# Karduino_Sch.net
KiCad netlist of a schematic drawn in Altium Designer
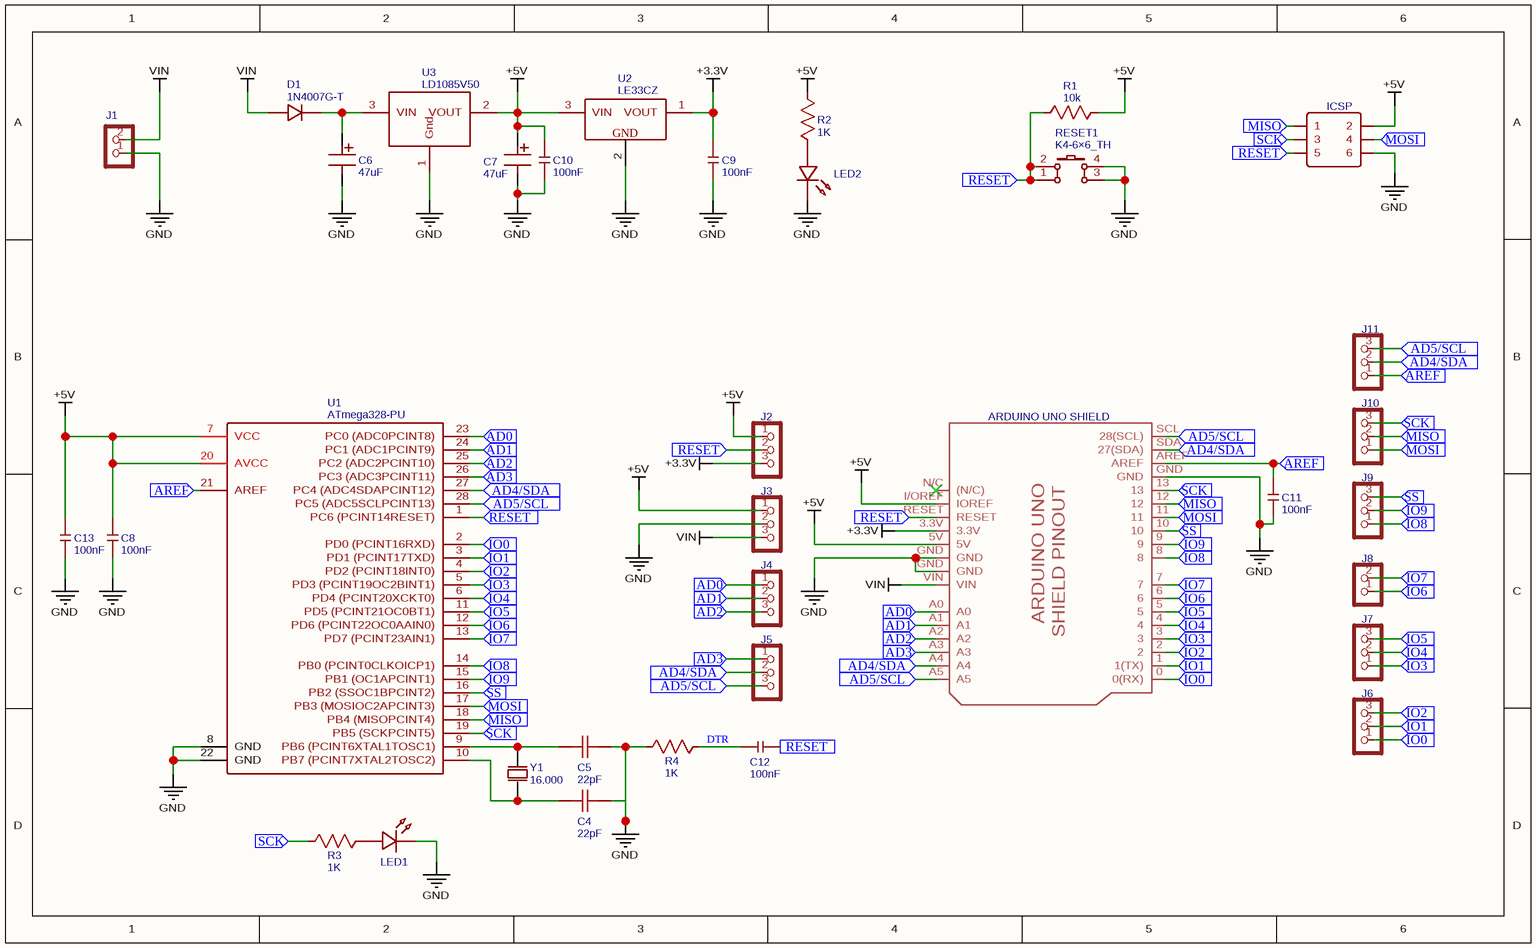
[diagram p0: Karduino_Sch.schdoc]

(export (version "E")
  (design (tool "Eeschema 10.0.6"))
  (components
    (comp (ref "C4")
      (value "22pF")
      (fields
        (field (name "MANUFACTURER") "TORCH(火炬)")
        (field (name "MANUFACTURER PART") "CC4-0805-CG-50V-22pF-J")
        (field (name "CONTRIBUTOR") "LCSC")
      )
      (libsource (lib "altium-import") (part "root_0_22pF_"))
    )
    (comp (ref "C5")
      (value "22pF")
      (fields
        (field (name "MANUFACTURER") "TORCH(火炬)")
        (field (name "MANUFACTURER PART") "CC4-0805-CG-50V-22pF-J")
        (field (name "CONTRIBUTOR") "LCSC")
      )
      (libsource (lib "altium-import") (part "root_0_22pF_"))
    )
    (comp (ref "C6")
      (value "47uF")
      (fields
        (field (name "VOLTAGE") "25V")
        (field (name "TOLERANCE") "±20%")
        (field (name "MANUFACTURER") "MULTICOMP")
        (field (name "CONTRIBUTOR") "Prof. Ing. F. Scordino")
      )
      (libsource (lib "altium-import") (part "root_3_47uF_"))
    )
    (comp (ref "C7")
      (value "47uF")
      (fields
        (field (name "VOLTAGE") "25V")
        (field (name "TOLERANCE") "±20%")
        (field (name "MANUFACTURER") "MULTICOMP")
        (field (name "CONTRIBUTOR") "Prof. Ing. F. Scordino")
      )
      (libsource (lib "altium-import") (part "root_3_47uF_"))
    )
    (comp (ref "C8")
      (value "100nF")
      (description "302010208")
      (fields (field (name "CONTRIBUTOR") "pitpossum 79"))
      (libsource (lib "altium-import") (part "root_1_100nF_"))
    )
    (comp (ref "C9")
      (value "100nF")
      (description "302010208")
      (fields (field (name "CONTRIBUTOR") "pitpossum 79"))
      (libsource (lib "altium-import") (part "root_1_100nF_"))
    )
    (comp (ref "C10")
      (value "100nF")
      (description "302010208")
      (fields (field (name "CONTRIBUTOR") "pitpossum 79"))
      (libsource (lib "altium-import") (part "root_1_100nF_"))
    )
    (comp (ref "C11")
      (value "100nF")
      (description "302010208")
      (fields (field (name "CONTRIBUTOR") "pitpossum 79"))
      (libsource (lib "altium-import") (part "root_1_100nF_"))
    )
    (comp (ref "C12")
      (value "100nF")
      (description "302010208")
      (fields (field (name "CONTRIBUTOR") "pitpossum 79"))
      (libsource (lib "altium-import") (part "root_0_100nF_"))
    )
    (comp (ref "C13")
      (value "100nF")
      (description "302010208")
      (fields (field (name "CONTRIBUTOR") "pitpossum 79"))
      (libsource (lib "altium-import") (part "root_1_100nF_"))
    )
    (comp (ref "D1")
      (value "1N4007G-T")
      (fields
        (field (name "MANUFACTURER") "Diodes Incorporated")
        (field (name "CONTRIBUTOR") "Habetamu Gezachew")
      )
      (libsource (lib "altium-import") (part "root_2_1N4007G-T_"))
    )
    (comp (ref "ICSP")
      (value "ICSP")
      (fields (field (name "MANUFACTURER") "BOOMELE(博穆精密)") (field (name "MANUFACTURER PART") "2.54-2*3P针"))
      (libsource (lib "altium-import") (part "root_0_ICSP_"))
    )
    (comp (ref "J1")
      (value "CON_TERMINAL_BLOCK_02-5MM")
      (description "2 poles wire to board terminal block")
      (fields (field (name "CONTRIBUTOR") "DangerousPrototype"))
      (libsource (lib "altium-import") (part "root_2_CON_TERMINAL_BLOCK_02-5MM_"))
    )
    (comp (ref "J2")
      (value "CON_TERMINAL_BLOCK_03-5MM")
      (description "3 poles, wire to board connector")
      (fields (field (name "CONTRIBUTOR") "DangerousPrototype"))
      (libsource (lib "altium-import") (part "root_0_CON_TERMINAL_BLOCK_03-5MM_"))
    )
    (comp (ref "J3")
      (value "CON_TERMINAL_BLOCK_03-5MM")
      (description "3 poles, wire to board connector")
      (fields (field (name "CONTRIBUTOR") "DangerousPrototype"))
      (libsource (lib "altium-import") (part "root_0_CON_TERMINAL_BLOCK_03-5MM_"))
    )
    (comp (ref "J4")
      (value "CON_TERMINAL_BLOCK_03-5MM")
      (description "3 poles, wire to board connector")
      (fields (field (name "CONTRIBUTOR") "DangerousPrototype"))
      (libsource (lib "altium-import") (part "root_0_CON_TERMINAL_BLOCK_03-5MM_"))
    )
    (comp (ref "J5")
      (value "CON_TERMINAL_BLOCK_03-5MM")
      (description "3 poles, wire to board connector")
      (fields (field (name "CONTRIBUTOR") "DangerousPrototype"))
      (libsource (lib "altium-import") (part "root_0_CON_TERMINAL_BLOCK_03-5MM_"))
    )
    (comp (ref "J6")
      (value "CON_TERMINAL_BLOCK_03-5MM")
      (description "3 poles, wire to board connector")
      (fields (field (name "CONTRIBUTOR") "DangerousPrototype"))
      (libsource (lib "altium-import") (part "root_2_CON_TERMINAL_BLOCK_03-5MM_"))
    )
    (comp (ref "J7")
      (value "CON_TERMINAL_BLOCK_03-5MM")
      (description "3 poles, wire to board connector")
      (fields (field (name "CONTRIBUTOR") "DangerousPrototype"))
      (libsource (lib "altium-import") (part "root_2_CON_TERMINAL_BLOCK_03-5MM_"))
    )
    (comp (ref "J8")
      (value "CON_TERMINAL_BLOCK_02-5MM")
      (description "2 poles wire to board terminal block")
      (fields (field (name "CONTRIBUTOR") "DangerousPrototype"))
      (libsource (lib "altium-import") (part "root_2_CON_TERMINAL_BLOCK_02-5MM_"))
    )
    (comp (ref "J9")
      (value "CON_TERMINAL_BLOCK_03-5MM")
      (description "3 poles, wire to board connector")
      (fields (field (name "CONTRIBUTOR") "DangerousPrototype"))
      (libsource (lib "altium-import") (part "root_2_CON_TERMINAL_BLOCK_03-5MM_"))
    )
    (comp (ref "J10")
      (value "CON_TERMINAL_BLOCK_03-5MM")
      (description "3 poles, wire to board connector")
      (fields (field (name "CONTRIBUTOR") "DangerousPrototype"))
      (libsource (lib "altium-import") (part "root_2_CON_TERMINAL_BLOCK_03-5MM_"))
    )
    (comp (ref "J11")
      (value "CON_TERMINAL_BLOCK_03-5MM")
      (description "3 poles, wire to board connector")
      (fields (field (name "CONTRIBUTOR") "DangerousPrototype"))
      (libsource (lib "altium-import") (part "root_2_CON_TERMINAL_BLOCK_03-5MM_"))
    )
    (comp (ref "LED1")
      (value "LED-TH-3mm_G")
      (fields
        (field (name "MANUFACTURER") "EVERLIGHT(台湾亿光)")
        (field (name "MANUFACTURER PART") "204-10SYGD/S530-E3")
        (field (name "CONTRIBUTOR") "LCEDA_Lib")
      )
      (libsource (lib "altium-import") (part "root_0_LED-TH-3mm_G_"))
    )
    (comp (ref "LED2")
      (value "LED-TH-3mm_R")
      (fields
        (field (name "MANUFACTURER") "EVERLIGHT(台湾亿光)")
        (field (name "MANUFACTURER PART") "204-10SDRD/S530-A3-L")
        (field (name "CONTRIBUTOR") "LCEDA_Lib")
      )
      (libsource (lib "altium-import") (part "root_3_LED-TH-3mm_R_"))
    )
    (comp (ref "PCB1")
      (value "ARDUINO UNO SHIELD")
      (fields (field (name "CONTRIBUTOR") "prodatasimulations"))
      (libsource (lib "altium-import") (part "root_0_ARDUINO UNO SHIELD_"))
    )
    (comp (ref "R1")
      (value "10k")
      (fields (field (name "CONTRIBUTOR") "LCEDA_Lib"))
      (libsource (lib "altium-import") (part "root_2_10k_"))
    )
    (comp (ref "R2")
      (value "1K")
      (fields (field (name "CONTRIBUTOR") "LCEDA_Lib"))
      (libsource (lib "altium-import") (part "root_1_1K_"))
    )
    (comp (ref "R3")
      (value "1K")
      (fields (field (name "CONTRIBUTOR") "LCEDA_Lib"))
      (libsource (lib "altium-import") (part "root_0_1K_"))
    )
    (comp (ref "R4")
      (value "1K")
      (fields (field (name "CONTRIBUTOR") "LCEDA_Lib"))
      (libsource (lib "altium-import") (part "root_0_1K_"))
    )
    (comp (ref "RESET1")
      (value "K4-6×6_TH")
      (fields
        (field (name "MANUFACTURER") "韩国韩荣")
        (field (name "MANUFACTURER PART") "K2-1102DP-E4SW-04")
        (field (name "CONTRIBUTOR") "LCEDA_Lib")
      )
      (libsource (lib "altium-import") (part "root_0_K4-6×6_TH_"))
    )
    (comp (ref "U1") (value "ATmega328-PU") (libsource (lib "altium-import") (part "root_0_ATmega328-PU_")))
    (comp (ref "U2")
      (value "LE33CZ")
      (description "Very Low Drop Voltage Regulators with Inhibit, 3.3V, 3-Pin TO92-INLINE, Tape and Reel")
      (libsource (lib "altium-import") (part "root_0_LE33CZ_"))
    )
    (comp (ref "U3")
      (value "LD1085V50")
      (fields (field (name "MANUFACTURER") "STMicroelectronics") (field (name "CONTRIBUTOR") "ih55t"))
      (libsource (lib "altium-import") (part "root_0_LD1085V50_"))
    )
    (comp (ref "Y1")
      (value "16.000")
      (fields
        (field (name "MANUFACTURER") "CTS(西迪斯)")
        (field (name "MANUFACTURER PART") "ATS098")
        (field (name "CONTRIBUTOR") "lcsc")
      )
      (libsource (lib "altium-import") (part "root_1_16.000_"))
    )
  )
  (nets
    (net (code "1") (name "+3.3V") (class "Default")
      (node (ref "C9") (pin "2") (pinfunction "2_2") (pintype "passive"))
      (node (ref "J2") (pin "3") (pinfunction "3_3") (pintype "passive"))
      (node (ref "PCB1") (pin "3.3V") (pinfunction "3.3V_3.3V") (pintype "passive"))
      (node (ref "U2") (pin "1") (pinfunction "VOUT_1") (pintype "passive"))
    )
    (net (code "2") (name "+5V") (class "Default")
      (node (ref "C10") (pin "2") (pinfunction "2_2") (pintype "passive"))
      (node (ref "C13") (pin "2") (pinfunction "2_2") (pintype "passive"))
      (node (ref "C7") (pin "1") (pinfunction "1_1") (pintype "passive"))
      (node (ref "C8") (pin "2") (pinfunction "2_2") (pintype "passive"))
      (node (ref "ICSP") (pin "2") (pinfunction "2_2") (pintype "passive"))
      (node (ref "J2") (pin "1") (pinfunction "1_1") (pintype "passive"))
      (node (ref "J3") (pin "1") (pinfunction "1_1") (pintype "passive"))
      (node (ref "PCB1") (pin "5V") (pinfunction "5V_5V") (pintype "passive"))
      (node (ref "PCB1") (pin "I/OREF") (pinfunction "IOREF_I/OREF") (pintype "passive"))
      (node (ref "R1") (pin "1") (pinfunction "1_1") (pintype "passive"))
      (node (ref "R2") (pin "2") (pinfunction "2_2") (pintype "passive"))
      (node (ref "U1") (pin "20") (pinfunction "AVCC_20") (pintype "passive"))
      (node (ref "U1") (pin "7") (pinfunction "VCC_7") (pintype "passive"))
      (node (ref "U2") (pin "3") (pinfunction "VIN_3") (pintype "passive"))
      (node (ref "U3") (pin "2") (pinfunction "VOUT_2") (pintype "passive"))
    )
    (net (code "3") (name "/AD0") (class "Default")
      (node (ref "J4") (pin "1") (pinfunction "1_1") (pintype "passive"))
      (node (ref "PCB1") (pin "A0") (pinfunction "A0_A0") (pintype "passive"))
      (node (ref "U1") (pin "23") (pinfunction "PC0_(ADC0PCINT8)_23") (pintype "passive"))
    )
    (net (code "4") (name "/AD1") (class "Default")
      (node (ref "J4") (pin "2") (pinfunction "2_2") (pintype "passive"))
      (node (ref "PCB1") (pin "A1") (pinfunction "A1_A1") (pintype "passive"))
      (node (ref "U1") (pin "24") (pinfunction "PC1_(ADC1PCINT9)_24") (pintype "passive"))
    )
    (net (code "5") (name "/AD2") (class "Default")
      (node (ref "J4") (pin "3") (pinfunction "3_3") (pintype "passive"))
      (node (ref "PCB1") (pin "A2") (pinfunction "A2_A2") (pintype "passive"))
      (node (ref "U1") (pin "25") (pinfunction "PC2_(ADC2PCINT10)_25") (pintype "passive"))
    )
    (net (code "6") (name "/AD3") (class "Default")
      (node (ref "J5") (pin "1") (pinfunction "1_1") (pintype "passive"))
      (node (ref "PCB1") (pin "A3") (pinfunction "A3_A3") (pintype "passive"))
      (node (ref "U1") (pin "26") (pinfunction "PC3_(ADC3PCINT11)_26") (pintype "passive"))
    )
    (net (code "7") (name "/AD4{slash}SDA") (class "Default")
      (node (ref "J11") (pin "2") (pinfunction "2_2") (pintype "passive"))
      (node (ref "J5") (pin "2") (pinfunction "2_2") (pintype "passive"))
      (node (ref "PCB1") (pin "A4") (pinfunction "A4_A4") (pintype "passive"))
      (node (ref "PCB1") (pin "SDA") (pinfunction "27(SDA)_SDA") (pintype "passive"))
      (node (ref "U1") (pin "27") (pinfunction "PC4_(ADC4SDAPCINT12)_27") (pintype "passive"))
    )
    (net (code "8") (name "/AD5{slash}SCL") (class "Default")
      (node (ref "J11") (pin "3") (pinfunction "3_3") (pintype "passive"))
      (node (ref "J5") (pin "3") (pinfunction "3_3") (pintype "passive"))
      (node (ref "PCB1") (pin "A5") (pinfunction "A5_A5") (pintype "passive"))
      (node (ref "PCB1") (pin "SCL") (pinfunction "28(SCL)_SCL") (pintype "passive"))
      (node (ref "U1") (pin "28") (pinfunction "PC5_(ADC5SCLPCINT13)_28") (pintype "passive"))
    )
    (net (code "9") (name "/AREF") (class "Default")
      (node (ref "C11") (pin "2") (pinfunction "2_2") (pintype "passive"))
      (node (ref "J11") (pin "1") (pinfunction "1_1") (pintype "passive"))
      (node (ref "PCB1") (pin "AREF") (pinfunction "AREF_AREF") (pintype "passive"))
      (node (ref "U1") (pin "21") (pinfunction "AREF_21") (pintype "passive"))
    )
    (net (code "10") (name "/DTR") (class "Default")
      (node (ref "C12") (pin "1") (pinfunction "1_1") (pintype "passive"))
      (node (ref "R4") (pin "2") (pinfunction "2_2") (pintype "passive"))
    )
    (net (code "11") (name "/IO0") (class "Default")
      (node (ref "J6") (pin "1") (pinfunction "1_1") (pintype "passive"))
      (node (ref "PCB1") (pin "0") (pinfunction "0(RX)_0") (pintype "passive"))
      (node (ref "U1") (pin "2") (pinfunction "PD0_(PCINT16RXD)_2") (pintype "passive"))
    )
    (net (code "12") (name "/IO1") (class "Default")
      (node (ref "J6") (pin "2") (pinfunction "2_2") (pintype "passive"))
      (node (ref "PCB1") (pin "1") (pinfunction "1(TX)_1") (pintype "passive"))
      (node (ref "U1") (pin "3") (pinfunction "PD1_(PCINT17TXD)_3") (pintype "passive"))
    )
    (net (code "13") (name "/IO2") (class "Default")
      (node (ref "J6") (pin "3") (pinfunction "3_3") (pintype "passive"))
      (node (ref "PCB1") (pin "2") (pinfunction "2_2") (pintype "passive"))
      (node (ref "U1") (pin "4") (pinfunction "PD2_(PCINT18INT0)_4") (pintype "passive"))
    )
    (net (code "14") (name "/IO3") (class "Default")
      (node (ref "J7") (pin "1") (pinfunction "1_1") (pintype "passive"))
      (node (ref "PCB1") (pin "3") (pinfunction "3_3") (pintype "passive"))
      (node (ref "U1") (pin "5") (pinfunction "PD3_(PCINT19OC2BINT1)_5") (pintype "passive"))
    )
    (net (code "15") (name "/IO4") (class "Default")
      (node (ref "J7") (pin "2") (pinfunction "2_2") (pintype "passive"))
      (node (ref "PCB1") (pin "4") (pinfunction "4_4") (pintype "passive"))
      (node (ref "U1") (pin "6") (pinfunction "PD4_(PCINT20XCKT0)_6") (pintype "passive"))
    )
    (net (code "16") (name "/IO5") (class "Default")
      (node (ref "J7") (pin "3") (pinfunction "3_3") (pintype "passive"))
      (node (ref "PCB1") (pin "5") (pinfunction "5_5") (pintype "passive"))
      (node (ref "U1") (pin "11") (pinfunction "PD5_(PCINT21OC0BT1)_11") (pintype "passive"))
    )
    (net (code "17") (name "/IO6") (class "Default")
      (node (ref "J8") (pin "1") (pinfunction "1_1") (pintype "passive"))
      (node (ref "PCB1") (pin "6") (pinfunction "6_6") (pintype "passive"))
      (node (ref "U1") (pin "12") (pinfunction "PD6_(PCINT22OC0AAIN0)_12") (pintype "passive"))
    )
    (net (code "18") (name "/IO7") (class "Default")
      (node (ref "J8") (pin "2") (pinfunction "2_2") (pintype "passive"))
      (node (ref "PCB1") (pin "7") (pinfunction "7_7") (pintype "passive"))
      (node (ref "U1") (pin "13") (pinfunction "PD7_(PCINT23AIN1)_13") (pintype "passive"))
    )
    (net (code "19") (name "/IO8") (class "Default")
      (node (ref "J9") (pin "1") (pinfunction "1_1") (pintype "passive"))
      (node (ref "PCB1") (pin "8") (pinfunction "8_8") (pintype "passive"))
      (node (ref "U1") (pin "14") (pinfunction "PB0_(PCINT0CLKOICP1)_14") (pintype "passive"))
    )
    (net (code "20") (name "/IO9") (class "Default")
      (node (ref "J9") (pin "2") (pinfunction "2_2") (pintype "passive"))
      (node (ref "PCB1") (pin "9") (pinfunction "9_9") (pintype "passive"))
      (node (ref "U1") (pin "15") (pinfunction "PB1_(OC1APCINT1)_15") (pintype "passive"))
    )
    (net (code "21") (name "/MISO") (class "Default")
      (node (ref "ICSP") (pin "1") (pinfunction "1_1") (pintype "passive"))
      (node (ref "J10") (pin "2") (pinfunction "2_2") (pintype "passive"))
      (node (ref "PCB1") (pin "12") (pinfunction "12_12") (pintype "passive"))
      (node (ref "U1") (pin "18") (pinfunction "PB4_(MISOPCINT4)_18") (pintype "passive"))
    )
    (net (code "22") (name "/MOSI") (class "Default")
      (node (ref "ICSP") (pin "4") (pinfunction "4_4") (pintype "passive"))
      (node (ref "J10") (pin "1") (pinfunction "1_1") (pintype "passive"))
      (node (ref "PCB1") (pin "11") (pinfunction "11_11") (pintype "passive"))
      (node (ref "U1") (pin "17") (pinfunction "PB3_(MOSIOC2APCINT3)_17") (pintype "passive"))
    )
    (net (code "23") (name "/RESET") (class "Default")
      (node (ref "C12") (pin "2") (pinfunction "2_2") (pintype "passive"))
      (node (ref "ICSP") (pin "5") (pinfunction "5_5") (pintype "passive"))
      (node (ref "J2") (pin "2") (pinfunction "2_2") (pintype "passive"))
      (node (ref "PCB1") (pin "RESET") (pinfunction "RESET_RESET") (pintype "passive"))
      (node (ref "R1") (pin "2") (pinfunction "2_2") (pintype "passive"))
      (node (ref "RESET1") (pin "1") (pinfunction "1_1") (pintype "passive"))
      (node (ref "RESET1") (pin "2") (pinfunction "2_2") (pintype "passive"))
      (node (ref "U1") (pin "1") (pinfunction "PC6_(PCINT14RESET)_1") (pintype "passive"))
    )
    (net (code "24") (name "/SCK") (class "Default")
      (node (ref "ICSP") (pin "3") (pinfunction "3_3") (pintype "passive"))
      (node (ref "J10") (pin "3") (pinfunction "3_3") (pintype "passive"))
      (node (ref "PCB1") (pin "13") (pinfunction "13_13") (pintype "passive"))
      (node (ref "R3") (pin "1") (pinfunction "1_1") (pintype "passive"))
      (node (ref "U1") (pin "19") (pinfunction "PB5_(SCKPCINT5)_19") (pintype "passive"))
    )
    (net (code "25") (name "/SS") (class "Default")
      (node (ref "J9") (pin "3") (pinfunction "3_3") (pintype "passive"))
      (node (ref "PCB1") (pin "10") (pinfunction "10_10") (pintype "passive"))
      (node (ref "U1") (pin "16") (pinfunction "PB2_(SSOC1BPCINT2)_16") (pintype "passive"))
    )
    (net (code "26") (name "GND") (class "Default")
      (node (ref "C10") (pin "1") (pinfunction "1_1") (pintype "passive"))
      (node (ref "C11") (pin "1") (pinfunction "1_1") (pintype "passive"))
      (node (ref "C13") (pin "1") (pinfunction "1_1") (pintype "passive"))
      (node (ref "C4") (pin "2") (pinfunction "2_2") (pintype "passive"))
      (node (ref "C5") (pin "2") (pinfunction "2_2") (pintype "passive"))
      (node (ref "C6") (pin "2") (pinfunction "2_2") (pintype "passive"))
      (node (ref "C7") (pin "2") (pinfunction "2_2") (pintype "passive"))
      (node (ref "C8") (pin "1") (pinfunction "1_1") (pintype "passive"))
      (node (ref "C9") (pin "1") (pinfunction "1_1") (pintype "passive"))
      (node (ref "ICSP") (pin "6") (pinfunction "6_6") (pintype "passive"))
      (node (ref "J1") (pin "1") (pinfunction "1_1") (pintype "passive"))
      (node (ref "J3") (pin "2") (pinfunction "2_2") (pintype "passive"))
      (node (ref "LED1") (pin "2") (pinfunction "2_2") (pintype "passive"))
      (node (ref "LED2") (pin "2") (pinfunction "2_2") (pintype "passive"))
      (node (ref "PCB1") (pin "GND") (pinfunction "GND_GND") (pintype "passive"))
      (node (ref "R4") (pin "1") (pinfunction "1_1") (pintype "passive"))
      (node (ref "RESET1") (pin "3") (pinfunction "3_3") (pintype "passive"))
      (node (ref "RESET1") (pin "4") (pinfunction "4_4") (pintype "passive"))
      (node (ref "U1") (pin "22") (pinfunction "GND_22") (pintype "passive"))
      (node (ref "U1") (pin "8") (pinfunction "GND_8") (pintype "passive"))
      (node (ref "U2") (pin "2") (pinfunction "GND_2") (pintype "passive"))
      (node (ref "U3") (pin "1") (pinfunction "Gnd_1") (pintype "passive"))
    )
    (net (code "27") (name "Net-(D1-K)") (class "Default")
      (node (ref "C6") (pin "1") (pinfunction "1_1") (pintype "passive"))
      (node (ref "D1") (pin "1") (pinfunction "K_1") (pintype "passive"))
      (node (ref "U3") (pin "3") (pinfunction "VIN_3") (pintype "passive"))
    )
    (net (code "28") (name "Net-(LED1-Pad1)") (class "Default")
      (node (ref "LED1") (pin "1") (pinfunction "1_1") (pintype "passive"))
      (node (ref "R3") (pin "2") (pinfunction "2_2") (pintype "passive"))
    )
    (net (code "29") (name "Net-(LED2-Pad1)") (class "Default")
      (node (ref "LED2") (pin "1") (pinfunction "1_1") (pintype "passive"))
      (node (ref "R2") (pin "1") (pinfunction "1_1") (pintype "passive"))
    )
    (net (code "30") (name "Net-(U1-PB6_(PCINT6XTAL1TOSC1))") (class "Default")
      (node (ref "C5") (pin "1") (pinfunction "1_1") (pintype "passive"))
      (node (ref "U1") (pin "9") (pinfunction "PB6_(PCINT6XTAL1TOSC1)_9") (pintype "passive"))
      (node (ref "Y1") (pin "2") (pinfunction "2_2") (pintype "passive"))
    )
    (net (code "31") (name "Net-(U1-PB7_(PCINT7XTAL2TOSC2))") (class "Default")
      (node (ref "C4") (pin "1") (pinfunction "1_1") (pintype "passive"))
      (node (ref "U1") (pin "10") (pinfunction "PB7_(PCINT7XTAL2TOSC2)_10") (pintype "passive"))
      (node (ref "Y1") (pin "1") (pinfunction "1_1") (pintype "passive"))
    )
    (net (code "32") (name "VIN") (class "Default")
      (node (ref "D1") (pin "2") (pinfunction "A_2") (pintype "passive"))
      (node (ref "J1") (pin "2") (pinfunction "2_2") (pintype "passive"))
      (node (ref "J3") (pin "3") (pinfunction "3_3") (pintype "passive"))
      (node (ref "PCB1") (pin "VIN") (pinfunction "VIN_VIN") (pintype "passive"))
    )
    (net (code "33") (name "unconnected-(PCB1-(N{slash}C)-PadN{slash}C)") (class "Default")
      (node (ref "PCB1") (pin "N/C") (pinfunction "(N/C)_N/C") (pintype "passive+no_connect"))
    )
  )
)
